# CRSC0004.net
KiCad netlist of a schematic drawn in Altium Designer
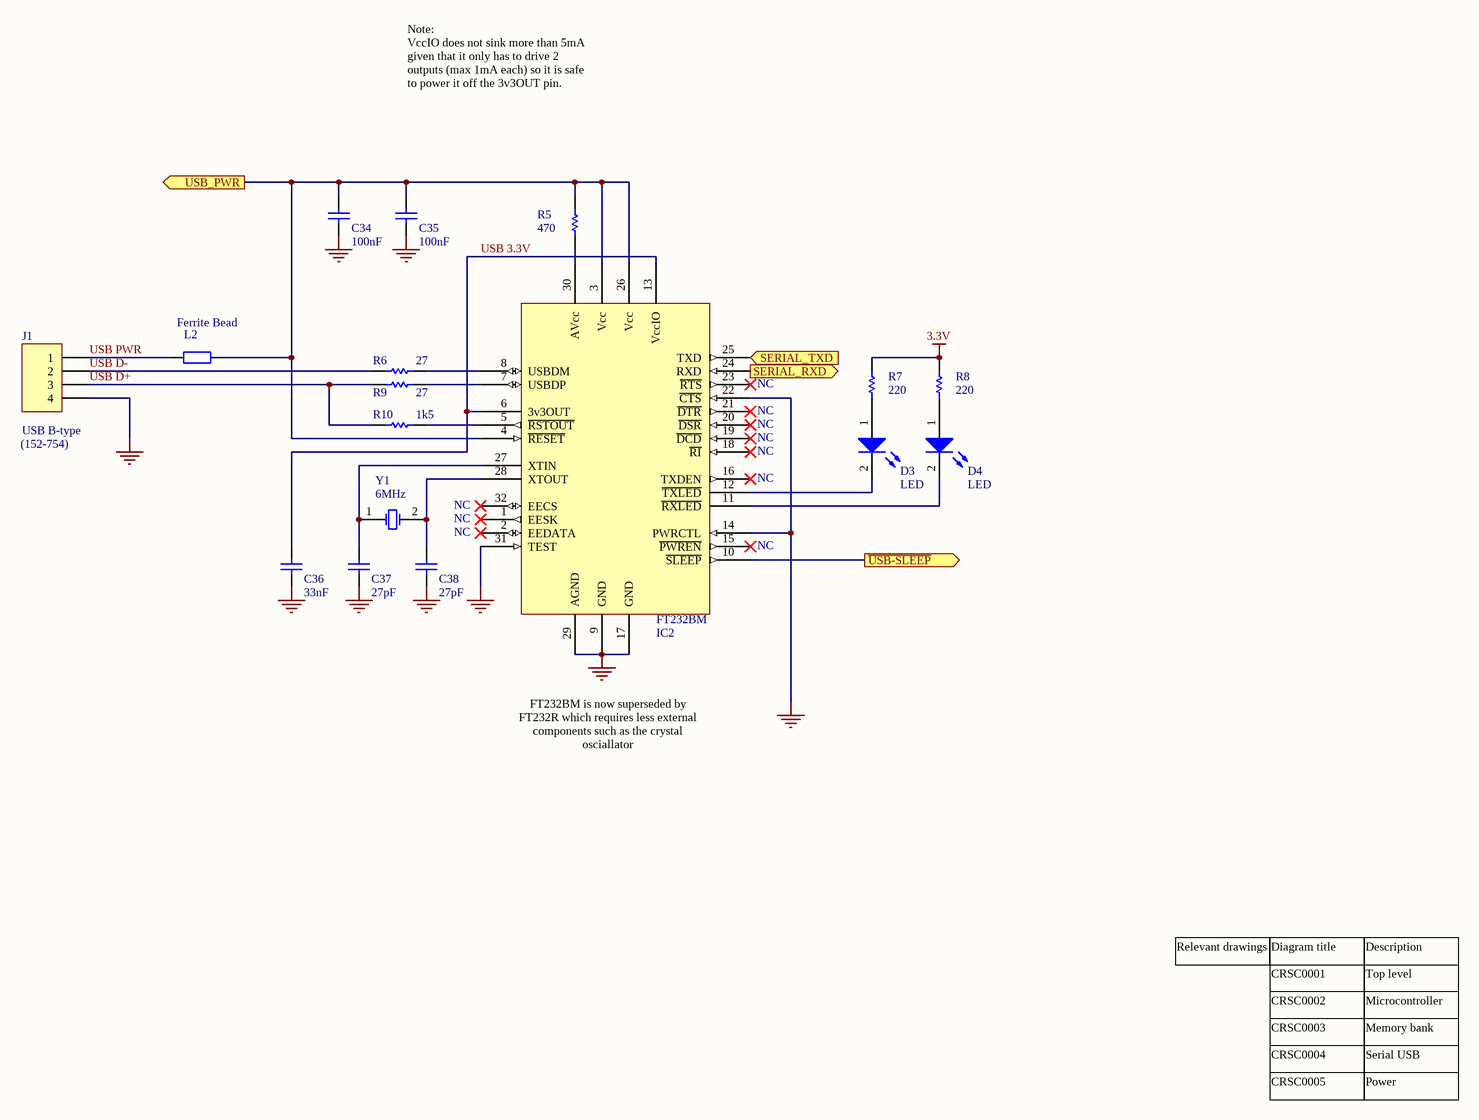
[diagram p0: CRSC0004.SchDoc]

(export (version "E")
  (design (tool "Eeschema 10.0.6"))
  (components
    (comp (ref "C34")
      (value "100nF")
      (footprint "0805")
      (description "Capacitor (Semiconductor SIM Model)")
      (fields
        (field (name "MANUFACTURER") "Generic Components")
        (field (name "PUBLISHER") "Altium Hobart Technology Centre")
      )
      (libsource (lib "Miscellaneous Devices") (part "Cap Semi"))
    )
    (comp (ref "C35")
      (value "100nF")
      (footprint "0805")
      (description "Capacitor (Semiconductor SIM Model)")
      (fields
        (field (name "MANUFACTURER") "Generic Components")
        (field (name "PUBLISHER") "Altium Hobart Technology Centre")
      )
      (libsource (lib "Miscellaneous Devices") (part "Cap Semi"))
    )
    (comp (ref "C36")
      (value "33nF")
      (footprint "0805")
      (description "Capacitor (Semiconductor SIM Model)")
      (fields
        (field (name "MANUFACTURER") "Generic Components")
        (field (name "PUBLISHER") "Altium Hobart Technology Centre")
      )
      (libsource (lib "Miscellaneous Devices") (part "Cap Semi"))
    )
    (comp (ref "C37")
      (value "27pF")
      (footprint "0805")
      (description "Capacitor (Semiconductor SIM Model)")
      (fields
        (field (name "MANUFACTURER") "Generic Components")
        (field (name "PUBLISHER") "Altium Hobart Technology Centre")
      )
      (libsource (lib "altium-import") (part "root_3_Cap Semi_"))
    )
    (comp (ref "C38")
      (value "27pF")
      (footprint "0805")
      (description "Capacitor (Semiconductor SIM Model)")
      (fields
        (field (name "MANUFACTURER") "Generic Components")
        (field (name "PUBLISHER") "Altium Hobart Technology Centre")
      )
      (libsource (lib "Miscellaneous Devices") (part "Cap Semi"))
    )
    (comp (ref "D3")
      (value "LED")
      (footprint "0805")
      (description "Typical RED, GREEN, YELLOW, AMBER GaAs LED")
      (fields
        (field (name "MANUFACTURER") "Generic Components")
        (field (name "PUBLISHER") "Altium Hobart Technology Centre")
      )
      (libsource (lib "Miscellaneous Devices") (part "LED2"))
    )
    (comp (ref "D4")
      (value "LED")
      (footprint "0805")
      (description "Typical RED, GREEN, YELLOW, AMBER GaAs LED")
      (fields
        (field (name "MANUFACTURER") "Generic Components")
        (field (name "PUBLISHER") "Altium Hobart Technology Centre")
      )
      (libsource (lib "Miscellaneous Devices") (part "LED2"))
    )
    (comp (ref "IC2")
      (value "FT232BM")
      (footprint "FT232BM")
      (description "FT232BM USB UART (Usb->Serial) IC")
      (libsource (lib "Components") (part "FT232BM"))
    )
    (comp (ref "J1")
      (value "USB B-type")
      (footprint "usb-b")
      (description "Header, 4-Pin")
      (fields (field (name "MANUFACTURER") "Generic Components"))
      (libsource (lib "Miscellaneous Connectors") (part "Header 4"))
    )
    (comp (ref "L2")
      (value "Ferrite Bead")
      (footprint "AXIAL-0.5")
      (fields
        (field (name "MANUFACTURER") "Generic Components")
        (field (name "PUBLISHER") "Altium Hobart Technology Centre")
      )
      (libsource (lib "Miscellaneous Devices") (part "Res2"))
    )
    (comp (ref "R5")
      (value "470")
      (footprint "0805")
      (description "Resistor")
      (fields
        (field (name "MANUFACTURER") "Generic Components")
        (field (name "PUBLISHER") "Altium Hobart Technology Centre")
      )
      (libsource (lib "Miscellaneous Devices") (part "Res1"))
    )
    (comp (ref "R6")
      (value "27")
      (footprint "0805")
      (description "Resistor")
      (fields
        (field (name "MANUFACTURER") "Generic Components")
        (field (name "PUBLISHER") "Altium Hobart Technology Centre")
      )
      (libsource (lib "Miscellaneous Devices") (part "Res1"))
    )
    (comp (ref "R7")
      (value "220")
      (footprint "0805")
      (description "Resistor")
      (fields
        (field (name "MANUFACTURER") "Generic Components")
        (field (name "PUBLISHER") "Altium Hobart Technology Centre")
      )
      (libsource (lib "Miscellaneous Devices") (part "Res1"))
    )
    (comp (ref "R8")
      (value "220")
      (footprint "0805")
      (description "Resistor")
      (fields
        (field (name "MANUFACTURER") "Generic Components")
        (field (name "PUBLISHER") "Altium Hobart Technology Centre")
      )
      (libsource (lib "Miscellaneous Devices") (part "Res1"))
    )
    (comp (ref "R9")
      (value "27")
      (footprint "0805")
      (description "Resistor")
      (fields
        (field (name "MANUFACTURER") "Generic Components")
        (field (name "PUBLISHER") "Altium Hobart Technology Centre")
      )
      (libsource (lib "Miscellaneous Devices") (part "Res1"))
    )
    (comp (ref "R10")
      (value "1k5")
      (footprint "0805")
      (description "Resistor")
      (fields
        (field (name "MANUFACTURER") "Generic Components")
        (field (name "PUBLISHER") "Altium Hobart Technology Centre")
      )
      (libsource (lib "Miscellaneous Devices") (part "Res1"))
    )
    (comp (ref "Y1")
      (value "6MHz")
      (footprint "HC49US")
      (description "Crystal Oscillator")
      (fields
        (field (name "MANUFACTURER") "Generic Components")
        (field (name "PUBLISHER") "Altium Hobart Technology Centre")
      )
      (libsource (lib "Miscellaneous Devices") (part "XTAL"))
    )
  )
  (nets
    (net (code "1") (name "/SERIAL_RXD") (class "Default")
      (node (ref "IC2") (pin "24") (pinfunction "RXD_24") (pintype "input"))
    )
    (net (code "2") (name "/SERIAL_TXD") (class "Default")
      (node (ref "IC2") (pin "25") (pinfunction "TXD_25") (pintype "output"))
    )
    (net (code "3") (name "/USB 3.3V") (class "Default")
      (node (ref "C36") (pin "1") (pinfunction "1_1") (pintype "passive"))
      (node (ref "IC2") (pin "13") (pinfunction "VccIO_13") (pintype "power_in"))
      (node (ref "IC2") (pin "6") (pinfunction "3v3OUT_6") (pintype "power_in"))
    )
    (net (code "4") (name "/USB D+") (class "Default")
      (node (ref "J1") (pin "3") (pinfunction "3_3") (pintype "passive"))
      (node (ref "R10") (pin "1") (pinfunction "1_1") (pintype "passive"))
      (node (ref "R9") (pin "1") (pinfunction "1_1") (pintype "passive"))
    )
    (net (code "5") (name "/USB D-") (class "Default")
      (node (ref "J1") (pin "2") (pinfunction "2_2") (pintype "passive"))
      (node (ref "R6") (pin "1") (pinfunction "1_1") (pintype "passive"))
    )
    (net (code "6") (name "/USB PWR") (class "Default")
      (node (ref "J1") (pin "1") (pinfunction "1_1") (pintype "passive"))
      (node (ref "L2") (pin "2") (pinfunction "2_2") (pintype "passive"))
    )
    (net (code "7") (name "/USB-SLEEP") (class "Default")
      (node (ref "IC2") (pin "10") (pinfunction "SLEEP_10") (pintype "output"))
    )
    (net (code "8") (name "/USB_PWR") (class "Default")
      (node (ref "C34") (pin "1") (pinfunction "1_1") (pintype "passive"))
      (node (ref "C35") (pin "1") (pinfunction "1_1") (pintype "passive"))
      (node (ref "IC2") (pin "26") (pinfunction "Vcc_26") (pintype "power_in"))
      (node (ref "IC2") (pin "3") (pinfunction "Vcc_3") (pintype "power_in"))
      (node (ref "IC2") (pin "4") (pinfunction "RESET_4") (pintype "input"))
      (node (ref "L2") (pin "1") (pinfunction "1_1") (pintype "passive"))
      (node (ref "R5") (pin "1") (pinfunction "1_1") (pintype "passive"))
    )
    (net (code "9") (name "3.3V") (class "Default")
      (node (ref "R7") (pin "1") (pinfunction "1_1") (pintype "passive"))
      (node (ref "R8") (pin "1") (pinfunction "1_1") (pintype "passive"))
    )
    (net (code "10") (name "GND") (class "Default")
      (node (ref "C34") (pin "2") (pinfunction "2_2") (pintype "passive"))
      (node (ref "C35") (pin "2") (pinfunction "2_2") (pintype "passive"))
      (node (ref "C36") (pin "2") (pinfunction "2_2") (pintype "passive"))
      (node (ref "C37") (pin "2") (pinfunction "2_2") (pintype "passive"))
      (node (ref "C38") (pin "2") (pinfunction "2_2") (pintype "passive"))
      (node (ref "IC2") (pin "14") (pinfunction "PWRCTL_14") (pintype "input"))
      (node (ref "IC2") (pin "17") (pinfunction "GND_17") (pintype "power_in"))
      (node (ref "IC2") (pin "22") (pinfunction "CTS_22") (pintype "input"))
      (node (ref "IC2") (pin "29") (pinfunction "AGND_29") (pintype "power_in"))
      (node (ref "IC2") (pin "31") (pinfunction "TEST_31") (pintype "input"))
      (node (ref "IC2") (pin "9") (pinfunction "GND_9") (pintype "power_in"))
      (node (ref "J1") (pin "4") (pinfunction "4_4") (pintype "passive"))
    )
    (net (code "11") (name "Net-(D3-A)") (class "Default")
      (node (ref "D3") (pin "1") (pinfunction "A_1") (pintype "passive"))
      (node (ref "R7") (pin "2") (pinfunction "2_2") (pintype "passive"))
    )
    (net (code "12") (name "Net-(D3-K)") (class "Default")
      (node (ref "D3") (pin "2") (pinfunction "K_2") (pintype "passive"))
      (node (ref "IC2") (pin "12") (pinfunction "TXLED_12") (pintype "open_collector"))
    )
    (net (code "13") (name "Net-(D4-A)") (class "Default")
      (node (ref "D4") (pin "1") (pinfunction "A_1") (pintype "passive"))
      (node (ref "R8") (pin "2") (pinfunction "2_2") (pintype "passive"))
    )
    (net (code "14") (name "Net-(D4-K)") (class "Default")
      (node (ref "D4") (pin "2") (pinfunction "K_2") (pintype "passive"))
      (node (ref "IC2") (pin "11") (pinfunction "RXLED_11") (pintype "open_collector"))
    )
    (net (code "15") (name "Net-(IC2-AVcc)") (class "Default")
      (node (ref "IC2") (pin "30") (pinfunction "AVcc_30") (pintype "power_in"))
      (node (ref "R5") (pin "2") (pinfunction "2_2") (pintype "passive"))
    )
    (net (code "16") (name "Net-(IC2-RSTOUT)") (class "Default")
      (node (ref "IC2") (pin "5") (pinfunction "RSTOUT_5") (pintype "output"))
      (node (ref "R10") (pin "2") (pinfunction "2_2") (pintype "passive"))
    )
    (net (code "17") (name "Net-(IC2-USBDM)") (class "Default")
      (node (ref "IC2") (pin "8") (pinfunction "USBDM_8") (pintype "bidirectional"))
      (node (ref "R6") (pin "2") (pinfunction "2_2") (pintype "passive"))
    )
    (net (code "18") (name "Net-(IC2-USBDP)") (class "Default")
      (node (ref "IC2") (pin "7") (pinfunction "USBDP_7") (pintype "bidirectional"))
      (node (ref "R9") (pin "2") (pinfunction "2_2") (pintype "passive"))
    )
    (net (code "19") (name "Net-(IC2-XTIN)") (class "Default")
      (node (ref "C37") (pin "1") (pinfunction "1_1") (pintype "passive"))
      (node (ref "IC2") (pin "27") (pinfunction "XTIN_27") (pintype "passive"))
      (node (ref "Y1") (pin "1") (pinfunction "OSC1_1") (pintype "passive"))
    )
    (net (code "20") (name "Net-(IC2-XTOUT)") (class "Default")
      (node (ref "C38") (pin "1") (pinfunction "1_1") (pintype "passive"))
      (node (ref "IC2") (pin "28") (pinfunction "XTOUT_28") (pintype "passive"))
      (node (ref "Y1") (pin "2") (pinfunction "OSC2_2") (pintype "passive"))
    )
    (net (code "21") (name "unconnected-(IC2-DCD-Pad19)") (class "Default")
      (node (ref "IC2") (pin "19") (pinfunction "DCD_19") (pintype "input+no_connect"))
    )
    (net (code "22") (name "unconnected-(IC2-DSR-Pad20)") (class "Default")
      (node (ref "IC2") (pin "20") (pinfunction "DSR_20") (pintype "input+no_connect"))
    )
    (net (code "23") (name "unconnected-(IC2-DTR-Pad21)") (class "Default")
      (node (ref "IC2") (pin "21") (pinfunction "DTR_21") (pintype "output+no_connect"))
    )
    (net (code "24") (name "unconnected-(IC2-EECS-Pad32)") (class "Default")
      (node (ref "IC2") (pin "32") (pinfunction "EECS_32") (pintype "bidirectional+no_connect"))
    )
    (net (code "25") (name "unconnected-(IC2-EEDATA-Pad2)") (class "Default")
      (node (ref "IC2") (pin "2") (pinfunction "EEDATA_2") (pintype "bidirectional+no_connect"))
    )
    (net (code "26") (name "unconnected-(IC2-EESK-Pad1)") (class "Default")
      (node (ref "IC2") (pin "1") (pinfunction "EESK_1") (pintype "output+no_connect"))
    )
    (net (code "27") (name "unconnected-(IC2-PWREN-Pad15)") (class "Default")
      (node (ref "IC2") (pin "15") (pinfunction "PWREN_15") (pintype "output+no_connect"))
    )
    (net (code "28") (name "unconnected-(IC2-RI-Pad18)") (class "Default")
      (node (ref "IC2") (pin "18") (pinfunction "RI_18") (pintype "input+no_connect"))
    )
    (net (code "29") (name "unconnected-(IC2-RTS-Pad23)") (class "Default")
      (node (ref "IC2") (pin "23") (pinfunction "RTS_23") (pintype "output+no_connect"))
    )
    (net (code "30") (name "unconnected-(IC2-TXDEN-Pad16)") (class "Default")
      (node (ref "IC2") (pin "16") (pinfunction "TXDEN_16") (pintype "output+no_connect"))
    )
  )
)
